# W028A.net
KiCad netlist of a schematic drawn in EAGLE
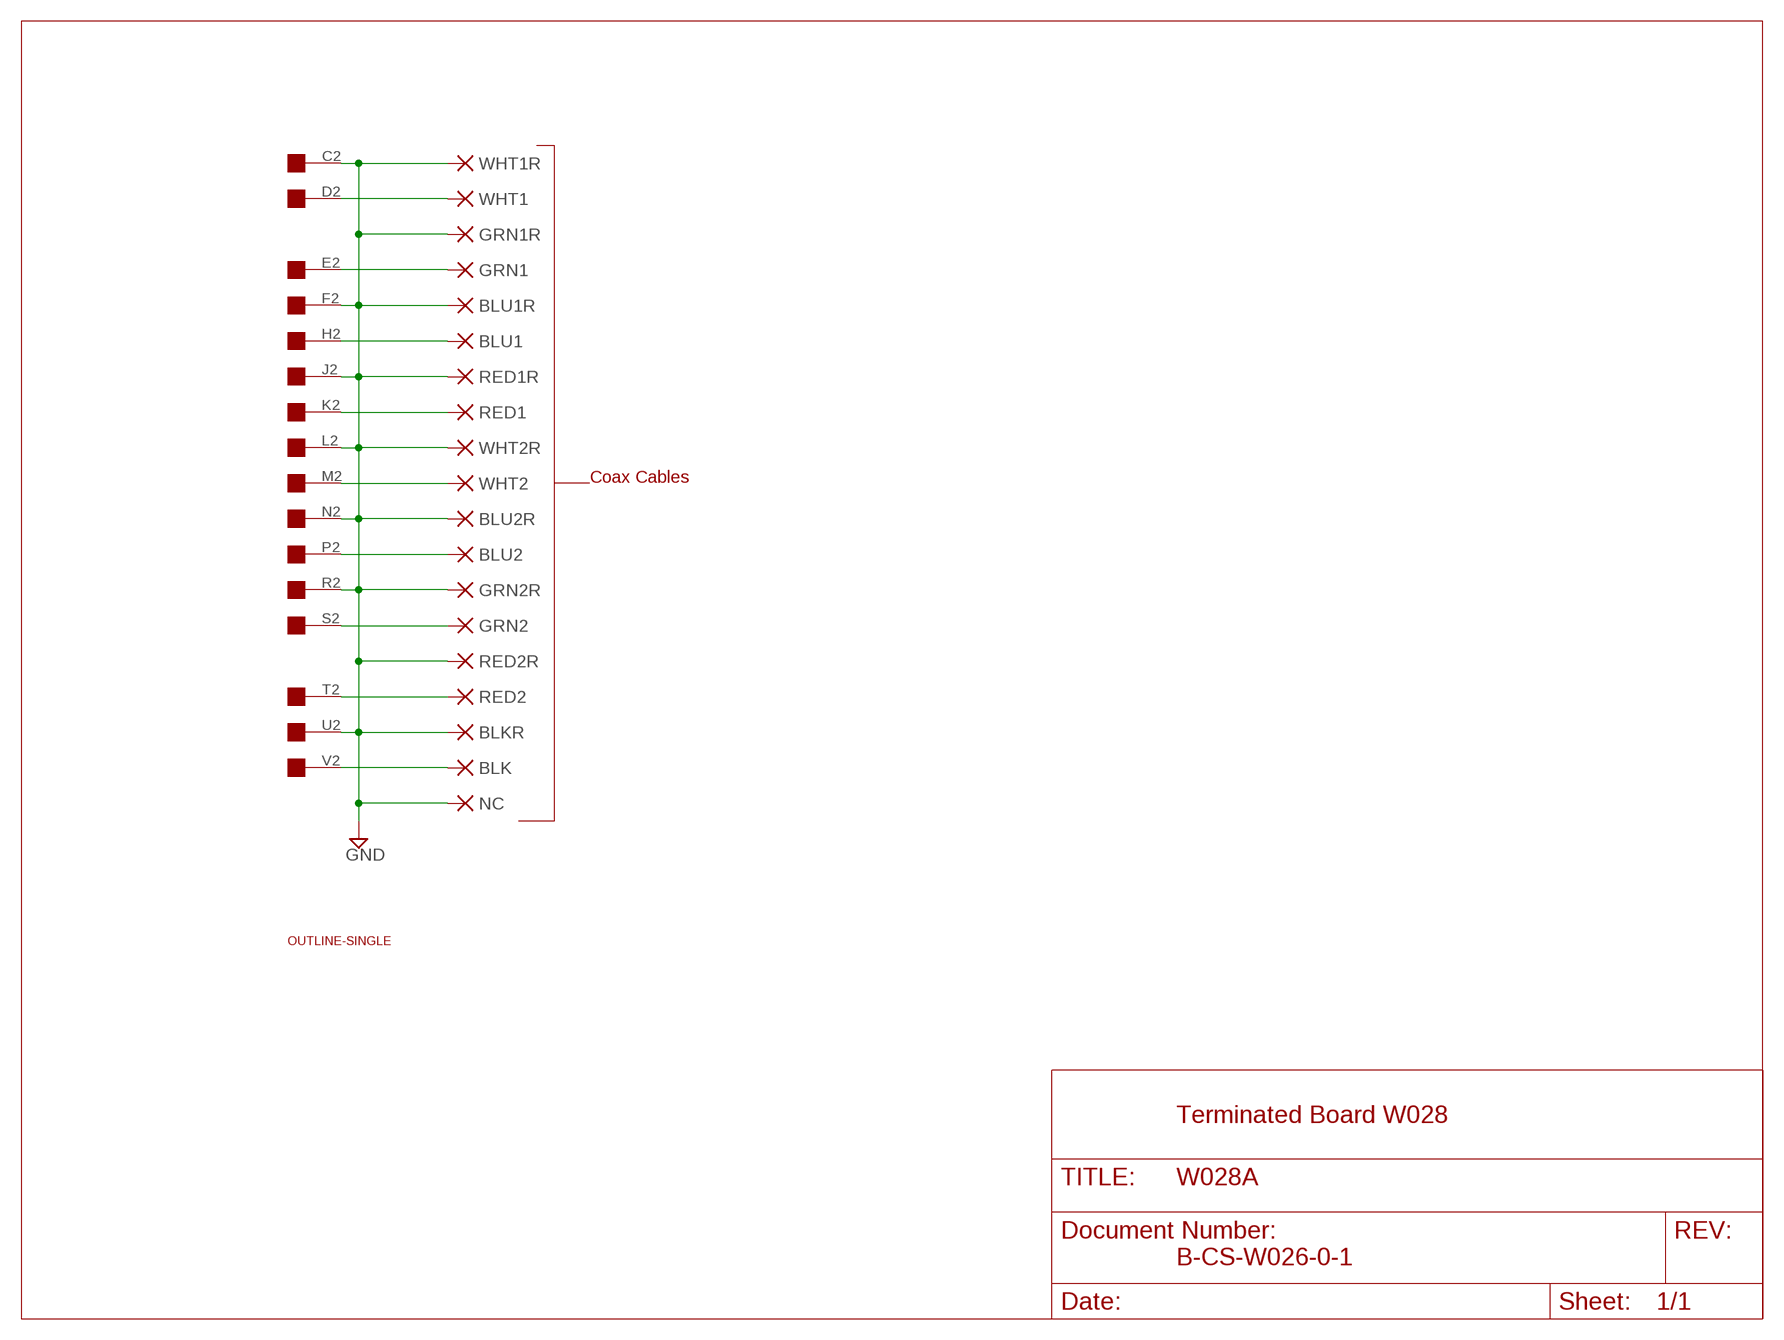
[diagram p0: schematic, sheet 1]

(export (version "E")
  (design (tool "Eeschema 10.0.6"))
  (components
    (comp (ref "BLK")
      (value "PAD-0465")
      (footprint "eagle-import:0465")
      (libsource (lib "eagle-import") (part "PAD-0465"))
    )
    (comp (ref "BLKR")
      (value "PAD-0465")
      (footprint "eagle-import:0465")
      (libsource (lib "eagle-import") (part "PAD-0465"))
    )
    (comp (ref "BLU1")
      (value "PAD-0465")
      (footprint "eagle-import:0465")
      (libsource (lib "eagle-import") (part "PAD-0465"))
    )
    (comp (ref "BLU1R")
      (value "PAD-0465")
      (footprint "eagle-import:0465")
      (libsource (lib "eagle-import") (part "PAD-0465"))
    )
    (comp (ref "BLU2")
      (value "PAD-0465")
      (footprint "eagle-import:0465")
      (libsource (lib "eagle-import") (part "PAD-0465"))
    )
    (comp (ref "BLU2R")
      (value "PAD-0465")
      (footprint "eagle-import:0465")
      (libsource (lib "eagle-import") (part "PAD-0465"))
    )
    (comp (ref "GRN1")
      (value "PAD-0465")
      (footprint "eagle-import:0465")
      (libsource (lib "eagle-import") (part "PAD-0465"))
    )
    (comp (ref "GRN1R")
      (value "PAD-0465")
      (footprint "eagle-import:0465")
      (libsource (lib "eagle-import") (part "PAD-0465"))
    )
    (comp (ref "GRN2")
      (value "PAD-0465")
      (footprint "eagle-import:0465")
      (libsource (lib "eagle-import") (part "PAD-0465"))
    )
    (comp (ref "GRN2R")
      (value "PAD-0465")
      (footprint "eagle-import:0465")
      (libsource (lib "eagle-import") (part "PAD-0465"))
    )
    (comp (ref "NC")
      (value "PAD-0465")
      (footprint "eagle-import:0465")
      (libsource (lib "eagle-import") (part "PAD-0465"))
    )
    (comp (ref "RED1")
      (value "PAD-0465")
      (footprint "eagle-import:0465")
      (libsource (lib "eagle-import") (part "PAD-0465"))
    )
    (comp (ref "RED1R")
      (value "PAD-0465")
      (footprint "eagle-import:0465")
      (libsource (lib "eagle-import") (part "PAD-0465"))
    )
    (comp (ref "RED2")
      (value "PAD-0465")
      (footprint "eagle-import:0465")
      (libsource (lib "eagle-import") (part "PAD-0465"))
    )
    (comp (ref "RED2R")
      (value "PAD-0465")
      (footprint "eagle-import:0465")
      (libsource (lib "eagle-import") (part "PAD-0465"))
    )
    (comp (ref "U$1")
      (value "OUTLINE-SINGLE")
      (footprint "eagle-import:SINGLE")
      (libsource (lib "eagle-import") (part "OUTLINE-SINGLE"))
    )
    (comp (ref "U$2")
      (value "EDGE-1")
      (footprint "eagle-import:EDGE-CON1")
      (libsource (lib "eagle-import") (part "EDGE-1"))
    )
    (comp (ref "WHT1")
      (value "PAD-0465")
      (footprint "eagle-import:0465")
      (libsource (lib "eagle-import") (part "PAD-0465"))
    )
    (comp (ref "WHT1R")
      (value "PAD-0465")
      (footprint "eagle-import:0465")
      (libsource (lib "eagle-import") (part "PAD-0465"))
    )
    (comp (ref "WHT2")
      (value "PAD-0465")
      (footprint "eagle-import:0465")
      (libsource (lib "eagle-import") (part "PAD-0465"))
    )
    (comp (ref "WHT2R")
      (value "PAD-0465")
      (footprint "eagle-import:0465")
      (libsource (lib "eagle-import") (part "PAD-0465"))
    )
  )
  (nets
    (net (code "1") (name "GND") (class "Default")
      (node (ref "BLKR") (pin "P$1") (pinfunction "P_P$1") (pintype "passive"))
      (node (ref "BLU1R") (pin "P$1") (pinfunction "P_P$1") (pintype "passive"))
      (node (ref "BLU2R") (pin "P$1") (pinfunction "P_P$1") (pintype "passive"))
      (node (ref "GRN1R") (pin "P$1") (pinfunction "P_P$1") (pintype "passive"))
      (node (ref "GRN2R") (pin "P$1") (pinfunction "P_P$1") (pintype "passive"))
      (node (ref "NC") (pin "P$1") (pinfunction "P_P$1") (pintype "passive"))
      (node (ref "RED1R") (pin "P$1") (pinfunction "P_P$1") (pintype "passive"))
      (node (ref "RED2R") (pin "P$1") (pinfunction "P_P$1") (pintype "passive"))
      (node (ref "U$2") (pin "C2") (pinfunction "1_C2") (pintype "bidirectional"))
      (node (ref "U$2") (pin "F2") (pinfunction "1_F2") (pintype "bidirectional"))
      (node (ref "U$2") (pin "J2") (pinfunction "1_J2") (pintype "bidirectional"))
      (node (ref "U$2") (pin "L2") (pinfunction "1_L2") (pintype "bidirectional"))
      (node (ref "U$2") (pin "N2") (pinfunction "1_N2") (pintype "bidirectional"))
      (node (ref "U$2") (pin "R2") (pinfunction "1_R2") (pintype "bidirectional"))
      (node (ref "U$2") (pin "U2") (pinfunction "1_U2") (pintype "bidirectional"))
      (node (ref "WHT1R") (pin "P$1") (pinfunction "P_P$1") (pintype "passive"))
      (node (ref "WHT2R") (pin "P$1") (pinfunction "P_P$1") (pintype "passive"))
    )
    (net (code "2") (name "Net-(BLK-P)") (class "Default")
      (node (ref "BLK") (pin "P$1") (pinfunction "P_P$1") (pintype "passive"))
      (node (ref "U$2") (pin "V2") (pinfunction "1_V2") (pintype "bidirectional"))
    )
    (net (code "3") (name "Net-(BLU1-P)") (class "Default")
      (node (ref "BLU1") (pin "P$1") (pinfunction "P_P$1") (pintype "passive"))
      (node (ref "U$2") (pin "H2") (pinfunction "1_H2") (pintype "bidirectional"))
    )
    (net (code "4") (name "Net-(BLU2-P)") (class "Default")
      (node (ref "BLU2") (pin "P$1") (pinfunction "P_P$1") (pintype "passive"))
      (node (ref "U$2") (pin "P2") (pinfunction "1_P2") (pintype "bidirectional"))
    )
    (net (code "5") (name "Net-(GRN1-P)") (class "Default")
      (node (ref "GRN1") (pin "P$1") (pinfunction "P_P$1") (pintype "passive"))
      (node (ref "U$2") (pin "E2") (pinfunction "1_E2") (pintype "bidirectional"))
    )
    (net (code "6") (name "Net-(GRN2-P)") (class "Default")
      (node (ref "GRN2") (pin "P$1") (pinfunction "P_P$1") (pintype "passive"))
      (node (ref "U$2") (pin "S2") (pinfunction "1_S2") (pintype "bidirectional"))
    )
    (net (code "7") (name "Net-(RED1-P)") (class "Default")
      (node (ref "RED1") (pin "P$1") (pinfunction "P_P$1") (pintype "passive"))
      (node (ref "U$2") (pin "K2") (pinfunction "1_K2") (pintype "bidirectional"))
    )
    (net (code "8") (name "Net-(RED2-P)") (class "Default")
      (node (ref "RED2") (pin "P$1") (pinfunction "P_P$1") (pintype "passive"))
      (node (ref "U$2") (pin "T2") (pinfunction "1_T2") (pintype "bidirectional"))
    )
    (net (code "9") (name "Net-(U$2D-1)") (class "Default")
      (node (ref "U$2") (pin "D2") (pinfunction "1_D2") (pintype "bidirectional"))
      (node (ref "WHT1") (pin "P$1") (pinfunction "P_P$1") (pintype "passive"))
    )
    (net (code "10") (name "Net-(U$2K-1)") (class "Default")
      (node (ref "U$2") (pin "M2") (pinfunction "1_M2") (pintype "bidirectional"))
      (node (ref "WHT2") (pin "P$1") (pinfunction "P_P$1") (pintype "passive"))
    )
  )
)
